# AmplifierPowerSupply.net
KiCad netlist of a schematic drawn in EAGLE
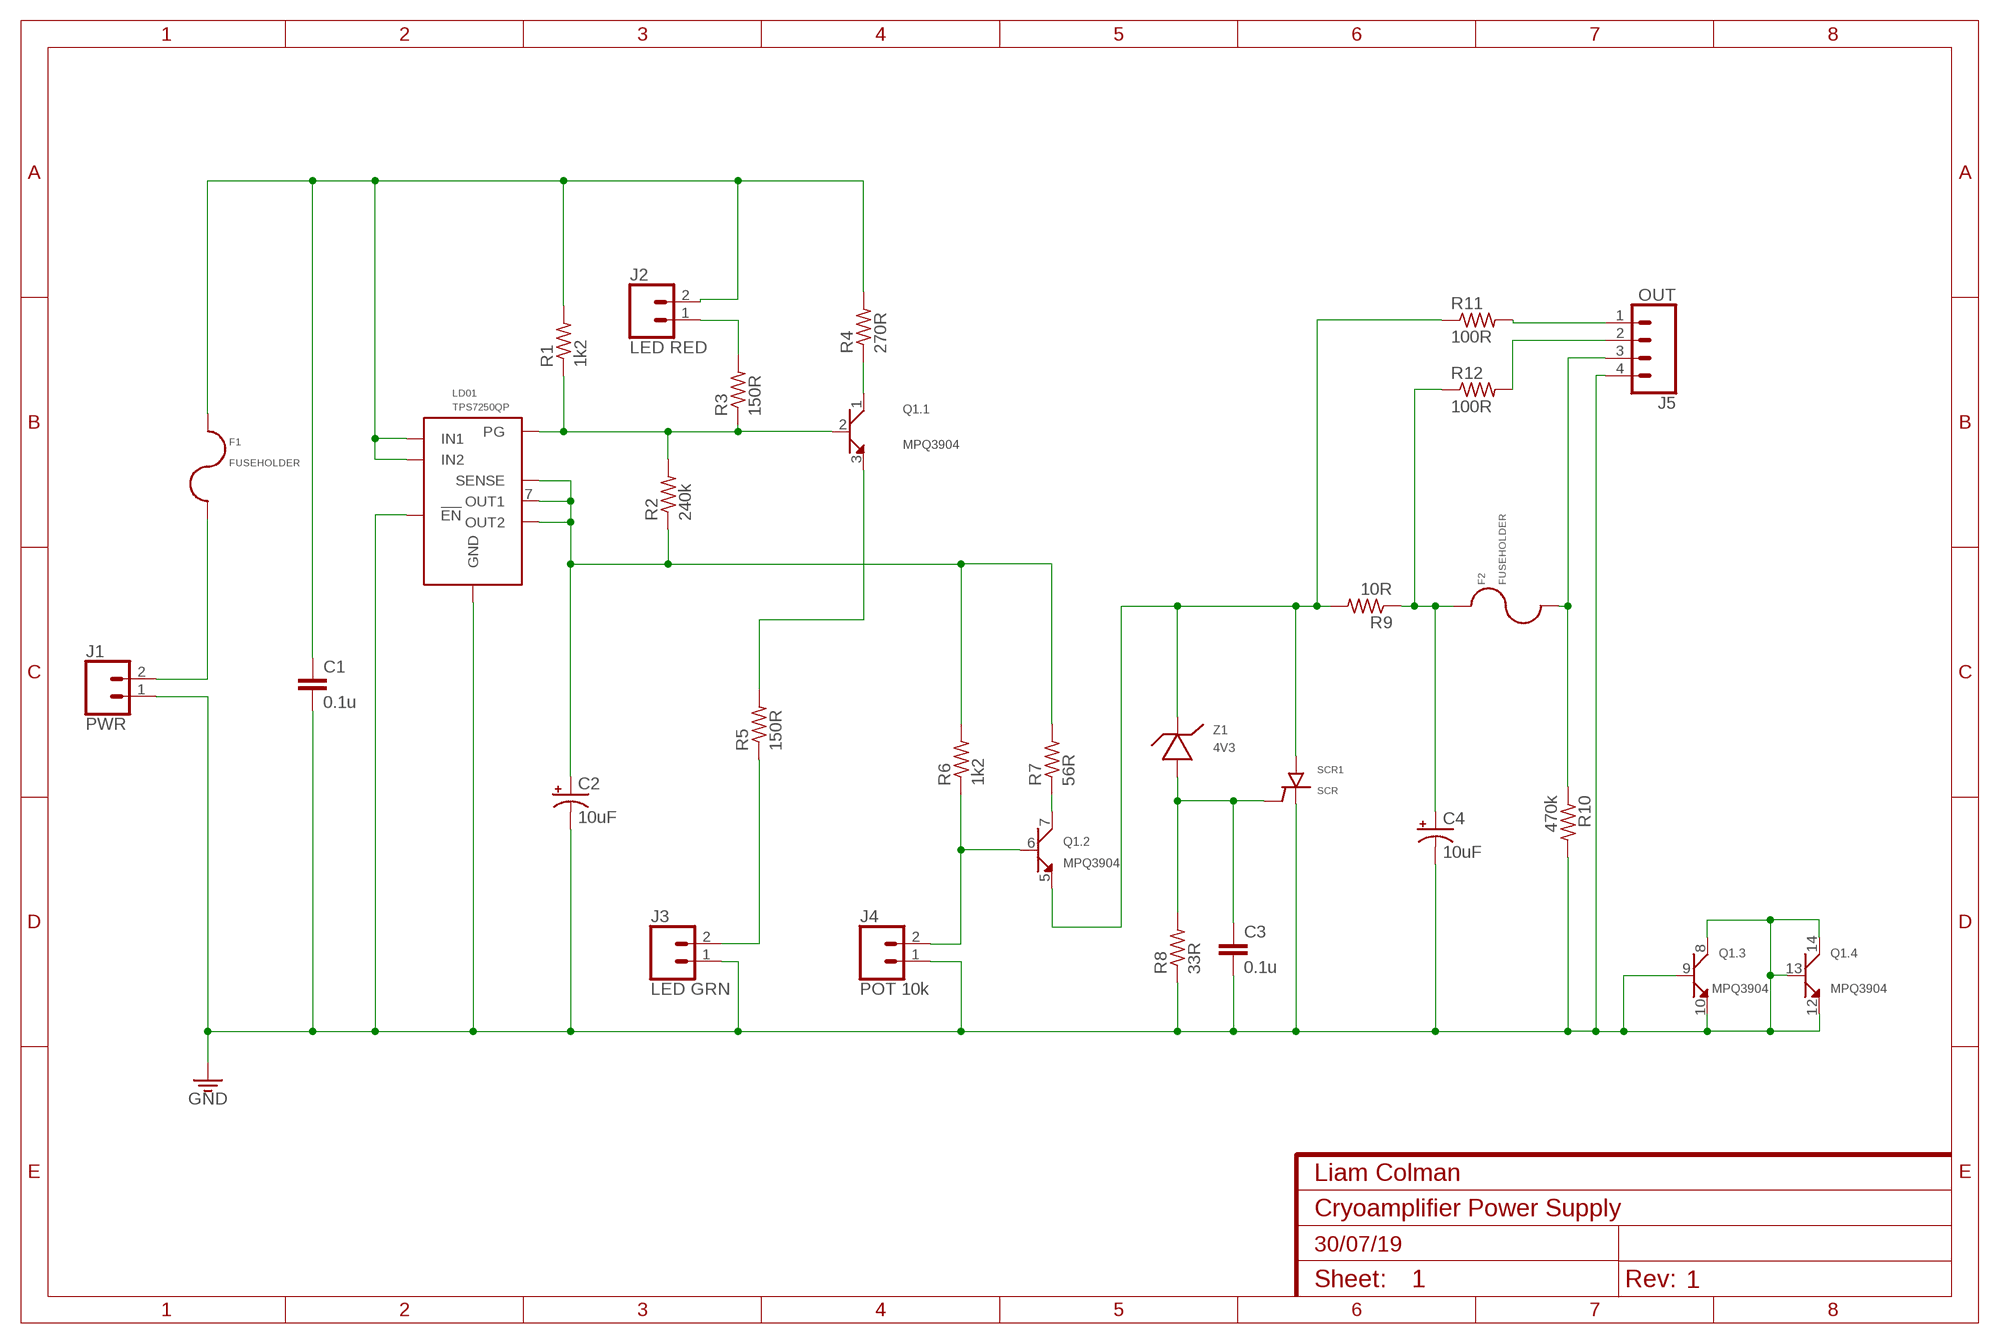
[diagram p0: schematic, sheet 1]

(export (version "E")
  (design (tool "Eeschema 10.0.6"))
  (components
    (comp (ref "C1")
      (value "0.1u")
      (footprint "eagle-import:C1206K")
      (libsource (lib "eagle-import") (part "C-EUC1206K"))
    )
    (comp (ref "C2")
      (value "10uF")
      (footprint "eagle-import:EIA3216")
      (libsource (lib "eagle-import") (part "10UF-POLAR-EIA3216-16V-10%(TANT)"))
    )
    (comp (ref "C3")
      (value "0.1u")
      (footprint "eagle-import:C1206K")
      (libsource (lib "eagle-import") (part "C-EUC1206K"))
    )
    (comp (ref "C4")
      (value "10uF")
      (footprint "eagle-import:EIA3216")
      (libsource (lib "eagle-import") (part "10UF-POLAR-EIA3216-16V-10%(TANT)"))
    )
    (comp (ref "F1")
      (value "FUSEHOLDER")
      (footprint "eagle-import:FUSEHOLDER")
      (libsource (lib "eagle-import") (part "FUSEHOLDER"))
    )
    (comp (ref "F2")
      (value "FUSEHOLDER")
      (footprint "eagle-import:FUSEHOLDER")
      (libsource (lib "eagle-import") (part "FUSEHOLDER"))
    )
    (comp (ref "FRAME1")
      (value "FRAMELIAM-A4")
      (footprint "eagle-import:DUMMY")
      (libsource (lib "eagle-import") (part "FRAMELIAM-A4"))
    )
    (comp (ref "J1")
      (value "PWR")
      (footprint "eagle-import:1X02")
      (libsource (lib "eagle-import") (part "CONN_02"))
    )
    (comp (ref "J2")
      (value "LED RED")
      (footprint "eagle-import:1X02")
      (libsource (lib "eagle-import") (part "CONN_02"))
    )
    (comp (ref "J3")
      (value "LED GRN")
      (footprint "eagle-import:1X02")
      (libsource (lib "eagle-import") (part "CONN_02"))
    )
    (comp (ref "J4")
      (value "POT 10k")
      (footprint "eagle-import:1X02")
      (libsource (lib "eagle-import") (part "CONN_02"))
    )
    (comp (ref "J5")
      (value "OUT")
      (footprint "eagle-import:1X04")
      (libsource (lib "eagle-import") (part "CONN_04PTH"))
    )
    (comp (ref "LD01")
      (value "TPS7250QP")
      (footprint "eagle-import:TPS7250QP")
      (libsource (lib "eagle-import") (part "LD01"))
    )
    (comp (ref "Q1")
      (value "MPQ3904")
      (footprint "eagle-import:MPQ3904")
      (libsource (lib "eagle-import") (part "MPQ3904"))
    )
    (comp (ref "R1")
      (value "1k2")
      (footprint "eagle-import:R0805")
      (libsource (lib "eagle-import") (part "R-US_R0805"))
    )
    (comp (ref "R2")
      (value "240k")
      (footprint "eagle-import:R0805")
      (libsource (lib "eagle-import") (part "R-US_R0805"))
    )
    (comp (ref "R3")
      (value "150R")
      (footprint "eagle-import:R0805")
      (libsource (lib "eagle-import") (part "R-US_R0805"))
    )
    (comp (ref "R4")
      (value "270R")
      (footprint "eagle-import:R0805")
      (libsource (lib "eagle-import") (part "R-US_R0805"))
    )
    (comp (ref "R5")
      (value "150R")
      (footprint "eagle-import:R0805")
      (libsource (lib "eagle-import") (part "R-US_R0805"))
    )
    (comp (ref "R6")
      (value "1k2")
      (footprint "eagle-import:R0805")
      (libsource (lib "eagle-import") (part "R-US_R0805"))
    )
    (comp (ref "R7")
      (value "56R")
      (footprint "eagle-import:R0805")
      (libsource (lib "eagle-import") (part "R-US_R0805"))
    )
    (comp (ref "R8")
      (value "33R")
      (footprint "eagle-import:R0805")
      (libsource (lib "eagle-import") (part "R-US_R0805"))
    )
    (comp (ref "R9")
      (value "10R")
      (footprint "eagle-import:R0805")
      (libsource (lib "eagle-import") (part "R-US_R0805"))
    )
    (comp (ref "R10")
      (value "470k")
      (footprint "eagle-import:R0805")
      (libsource (lib "eagle-import") (part "R-US_R0805"))
    )
    (comp (ref "R11")
      (value "100R")
      (footprint "eagle-import:R0805")
      (libsource (lib "eagle-import") (part "R-US_R0805"))
    )
    (comp (ref "R12")
      (value "100R")
      (footprint "eagle-import:R0805")
      (libsource (lib "eagle-import") (part "R-US_R0805"))
    )
    (comp (ref "SCR1")
      (value "SCR")
      (footprint "eagle-import:TO-92")
      (libsource (lib "eagle-import") (part "SCR"))
    )
    (comp (ref "Z1")
      (value "4V3")
      (footprint "eagle-import:DZ2W04300L")
      (libsource (lib "eagle-import") (part "ZENERDIODESMD"))
    )
  )
  (nets
    (net (code "1") (name "GND") (class "Default")
      (node (ref "C1") (pin "2") (pinfunction "2_2") (pintype "passive"))
      (node (ref "C2") (pin "-") (pinfunction "-_-") (pintype "passive"))
      (node (ref "C3") (pin "2") (pinfunction "2_2") (pintype "passive"))
      (node (ref "C4") (pin "-") (pinfunction "-_-") (pintype "passive"))
      (node (ref "J1") (pin "1") (pinfunction "1_1") (pintype "passive"))
      (node (ref "J3") (pin "1") (pinfunction "1_1") (pintype "passive"))
      (node (ref "J4") (pin "1") (pinfunction "1_1") (pintype "passive"))
      (node (ref "J5") (pin "4") (pinfunction "4_4") (pintype "passive"))
      (node (ref "LD01") (pin "3") (pinfunction "GND_3") (pintype "bidirectional"))
      (node (ref "LD01") (pin "4") (pinfunction "~{EN}_4") (pintype "bidirectional"))
      (node (ref "Q1") (pin "10") (pinfunction "EMITTER_10") (pintype "bidirectional"))
      (node (ref "Q1") (pin "12") (pinfunction "EMITTER_12") (pintype "bidirectional"))
      (node (ref "Q1") (pin "13") (pinfunction "BASE_13") (pintype "bidirectional"))
      (node (ref "Q1") (pin "14") (pinfunction "COLLECTOR_14") (pintype "bidirectional"))
      (node (ref "Q1") (pin "8") (pinfunction "COLLECTOR_8") (pintype "bidirectional"))
      (node (ref "Q1") (pin "9") (pinfunction "BASE_9") (pintype "bidirectional"))
      (node (ref "R10") (pin "2") (pinfunction "2_2") (pintype "passive"))
      (node (ref "R8") (pin "1") (pinfunction "1_1") (pintype "passive"))
      (node (ref "SCR1") (pin "K") (pinfunction "CATHODE_K") (pintype "bidirectional"))
    )
    (net (code "2") (name "Net-(C4-Pad+)") (class "Default")
      (node (ref "C4") (pin "+") (pinfunction "+_+") (pintype "passive"))
      (node (ref "F2") (pin "P$1") (pinfunction "P$1_P$1") (pintype "bidirectional"))
      (node (ref "R12") (pin "1") (pinfunction "1_1") (pintype "passive"))
      (node (ref "R9") (pin "1") (pinfunction "1_1") (pintype "passive"))
    )
    (net (code "3") (name "Net-(F1-PadP$2)") (class "Default")
      (node (ref "F1") (pin "P$2") (pinfunction "P$2_P$2") (pintype "bidirectional"))
      (node (ref "J1") (pin "2") (pinfunction "2_2") (pintype "passive"))
    )
    (net (code "4") (name "Net-(F2-PadP$2)") (class "Default")
      (node (ref "F2") (pin "P$2") (pinfunction "P$2_P$2") (pintype "bidirectional"))
      (node (ref "J5") (pin "3") (pinfunction "3_3") (pintype "passive"))
      (node (ref "R10") (pin "1") (pinfunction "1_1") (pintype "passive"))
    )
    (net (code "5") (name "Net-(J2-Pad1)") (class "Default")
      (node (ref "J2") (pin "1") (pinfunction "1_1") (pintype "passive"))
      (node (ref "R3") (pin "2") (pinfunction "2_2") (pintype "passive"))
    )
    (net (code "6") (name "Net-(J3-Pad2)") (class "Default")
      (node (ref "J3") (pin "2") (pinfunction "2_2") (pintype "passive"))
      (node (ref "R5") (pin "1") (pinfunction "1_1") (pintype "passive"))
    )
    (net (code "7") (name "Net-(J5-Pad1)") (class "Default")
      (node (ref "J5") (pin "1") (pinfunction "1_1") (pintype "passive"))
      (node (ref "R11") (pin "2") (pinfunction "2_2") (pintype "passive"))
    )
    (net (code "8") (name "Net-(J5-Pad2)") (class "Default")
      (node (ref "J5") (pin "2") (pinfunction "2_2") (pintype "passive"))
      (node (ref "R12") (pin "2") (pinfunction "2_2") (pintype "passive"))
    )
    (net (code "9") (name "Net-(LD01-IN1)") (class "Default")
      (node (ref "C1") (pin "1") (pinfunction "1_1") (pintype "passive"))
      (node (ref "F1") (pin "P$1") (pinfunction "P$1_P$1") (pintype "bidirectional"))
      (node (ref "J2") (pin "2") (pinfunction "2_2") (pintype "passive"))
      (node (ref "LD01") (pin "5") (pinfunction "IN1_5") (pintype "input"))
      (node (ref "LD01") (pin "6") (pinfunction "IN2_6") (pintype "input"))
      (node (ref "R1") (pin "2") (pinfunction "2_2") (pintype "passive"))
      (node (ref "R4") (pin "2") (pinfunction "2_2") (pintype "passive"))
    )
    (net (code "10") (name "Net-(LD01-OUT1)") (class "Default")
      (node (ref "C2") (pin "+") (pinfunction "+_+") (pintype "passive"))
      (node (ref "LD01") (pin "1") (pinfunction "SENSE_1") (pintype "bidirectional"))
      (node (ref "LD01") (pin "7") (pinfunction "OUT1_7") (pintype "output"))
      (node (ref "LD01") (pin "8") (pinfunction "OUT2_8") (pintype "output"))
      (node (ref "R2") (pin "1") (pinfunction "1_1") (pintype "passive"))
      (node (ref "R6") (pin "2") (pinfunction "2_2") (pintype "passive"))
      (node (ref "R7") (pin "2") (pinfunction "2_2") (pintype "passive"))
    )
    (net (code "11") (name "Net-(LD01-PG)") (class "Default")
      (node (ref "LD01") (pin "2") (pinfunction "PG_2") (pintype "bidirectional"))
      (node (ref "Q1") (pin "2") (pinfunction "BASE_2") (pintype "bidirectional"))
      (node (ref "R1") (pin "1") (pinfunction "1_1") (pintype "passive"))
      (node (ref "R2") (pin "2") (pinfunction "2_2") (pintype "passive"))
      (node (ref "R3") (pin "1") (pinfunction "1_1") (pintype "passive"))
    )
    (net (code "12") (name "Net-(Q1A-COLLECTOR)") (class "Default")
      (node (ref "Q1") (pin "1") (pinfunction "COLLECTOR_1") (pintype "bidirectional"))
      (node (ref "R4") (pin "1") (pinfunction "1_1") (pintype "passive"))
    )
    (net (code "13") (name "Net-(Q1A-EMITTER)") (class "Default")
      (node (ref "Q1") (pin "3") (pinfunction "EMITTER_3") (pintype "bidirectional"))
      (node (ref "R5") (pin "2") (pinfunction "2_2") (pintype "passive"))
    )
    (net (code "14") (name "Net-(Q1B-BASE)") (class "Default")
      (node (ref "J4") (pin "2") (pinfunction "2_2") (pintype "passive"))
      (node (ref "Q1") (pin "6") (pinfunction "BASE_6") (pintype "bidirectional"))
      (node (ref "R6") (pin "1") (pinfunction "1_1") (pintype "passive"))
    )
    (net (code "15") (name "Net-(Q1B-COLLECTOR)") (class "Default")
      (node (ref "Q1") (pin "7") (pinfunction "COLLECTOR_7") (pintype "bidirectional"))
      (node (ref "R7") (pin "1") (pinfunction "1_1") (pintype "passive"))
    )
    (net (code "16") (name "Net-(Q1B-EMITTER)") (class "Default")
      (node (ref "Q1") (pin "5") (pinfunction "EMITTER_5") (pintype "bidirectional"))
      (node (ref "R11") (pin "1") (pinfunction "1_1") (pintype "passive"))
      (node (ref "R9") (pin "2") (pinfunction "2_2") (pintype "passive"))
      (node (ref "SCR1") (pin "A") (pinfunction "ANODE_A") (pintype "bidirectional"))
      (node (ref "Z1") (pin "1") (pinfunction "CATHODE_1") (pintype "bidirectional"))
    )
    (net (code "17") (name "Net-(SCR1-GATE)") (class "Default")
      (node (ref "C3") (pin "1") (pinfunction "1_1") (pintype "passive"))
      (node (ref "R8") (pin "2") (pinfunction "2_2") (pintype "passive"))
      (node (ref "SCR1") (pin "G") (pinfunction "GATE_G") (pintype "bidirectional"))
      (node (ref "Z1") (pin "2") (pinfunction "ANODE_2") (pintype "bidirectional"))
    )
  )
)
